# Interfaces.net
KiCad netlist of a schematic drawn in Altium Designer
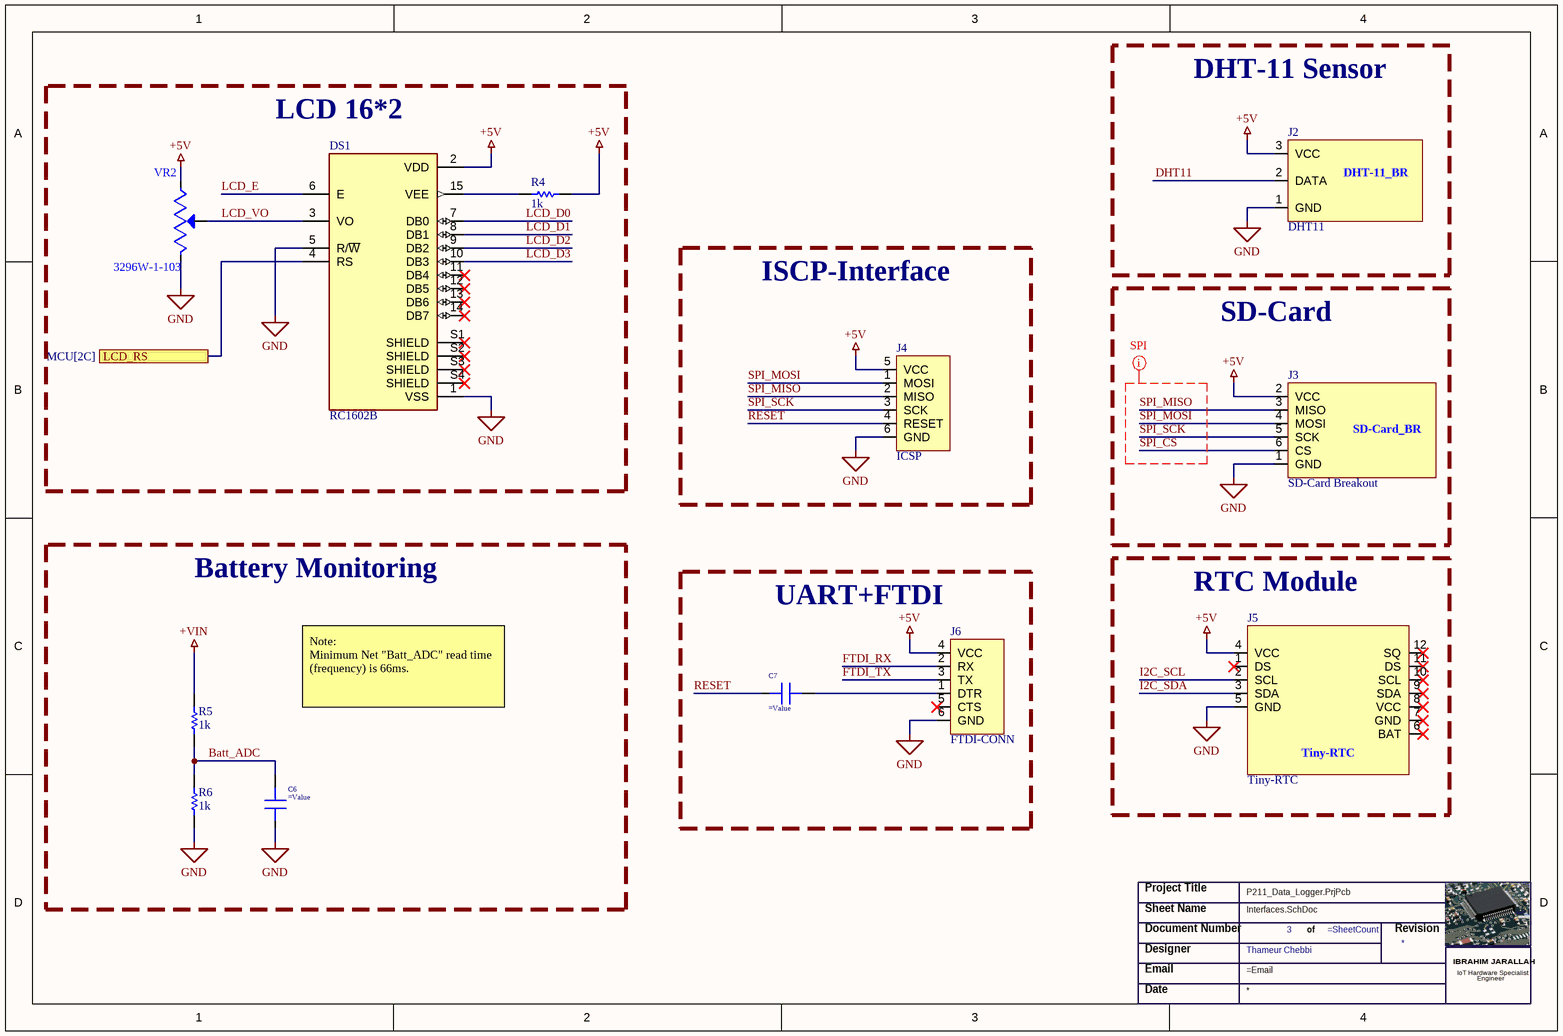
[diagram p0: Interfaces.SchDoc]

(export (version "E")
  (design (tool "Eeschema 10.0.6"))
  (components
    (comp (ref "C6")
      (value "~")
      (footprint "C 0805(2012)x0.85")
      (description "SMD 0805     50V X7R 10%")
      (fields (field (name "MANUFACTURER") "Samsung") (field (name "PUBLISHER") "Hefest"))
      (libsource (lib "SCH_THA") (part "C 0805    50V X7R - 0*"))
    )
    (comp (ref "C7")
      (value "~")
      (footprint "C 0805(2012)x0.85")
      (description "SMD 0805     50V X7R 10%")
      (fields (field (name "MANUFACTURER") "Samsung") (field (name "PUBLISHER") "Hefest"))
      (libsource (lib "SCH_THA") (part "C 0805    50V X7R - 0*"))
    )
    (comp (ref "DS1")
      (value "RC1602B")
      (footprint "LCD_RC1602B-BIW-CSV")
      (description "Display: LCD; alphanumeric; STN Negative; 16x2; blue; LED; PIN: 16")
      (fields (field (name "MF") "{'manufacturer': u'Raystar'}") (field (name "MP") "RC1602B-BIW-CSV"))
      (libsource (lib "SCH_THA") (part "RC1602B-BIW-CSV"))
    )
    (comp (ref "J2") (value "DHT11") (footprint "DHT11-BREAKOUT") (libsource (lib "SCH_THA") (part "DHT11")))
    (comp (ref "J3")
      (value "SD-Card Breakout")
      (footprint "SD-Card Breakout")
      (libsource (lib "SCH_THA") (part "SD-Card Breakout"))
    )
    (comp (ref "J4")
      (value "ICSP")
      (footprint "FTDI")
      (description "ICSP-CONN")
      (libsource (lib "SCH_THA") (part "ICSP"))
    )
    (comp (ref "J5")
      (value "Tiny-RTC")
      (footprint "Tiny-RTC")
      (libsource (lib "SCH_THA") (part "Tiny-RTC Breakout Board"))
    )
    (comp (ref "J6") (value "FTDI-CONN") (footprint "FTDI") (libsource (lib "SCH_THA") (part "FTDI")))
    (comp (ref "R4")
      (value "1k")
      (footprint "RESC2013X50X30LL20T20")
      (libsource (lib "SCH_THA") (part "RES-0805-SMD"))
    )
    (comp (ref "R5")
      (value "1k")
      (footprint "FP-CRCW1206-e3-IPC_B")
      (libsource (lib "SCH_THA") (part "RES-1206-SMD"))
    )
    (comp (ref "R6")
      (value "1k")
      (footprint "FP-CRCW1206-e3-IPC_B")
      (libsource (lib "SCH_THA") (part "RES-1206-SMD"))
    )
    (comp (ref "VR2")
      (value "3296W-1-103")
      (footprint "TRIM_3296W-1-103")
      (fields (field (name "MF") "{'manufacturer': u'Bourns'}"))
      (libsource (lib "3296W-1-103") (part "3296W-1-103"))
    )
  )
  (nets
    (net (code "1") (name "+5V") (class "Default")
      (node (ref "DS1") (pin "2") (pinfunction "VDD_2") (pintype "power_in"))
      (node (ref "J2") (pin "3") (pinfunction "VCC_3") (pintype "passive"))
      (node (ref "J3") (pin "2") (pinfunction "VCC_2") (pintype "passive"))
      (node (ref "J4") (pin "5") (pinfunction "VCC_5") (pintype "passive"))
      (node (ref "J5") (pin "4") (pinfunction "VCC_4") (pintype "passive"))
      (node (ref "J6") (pin "4") (pinfunction "VCC_4") (pintype "power_in"))
      (node (ref "R4") (pin "1") (pinfunction "1_1") (pintype "passive"))
      (node (ref "VR2") (pin "3") (pinfunction "CW_3") (pintype "passive"))
    )
    (net (code "2") (name "+VIN") (class "Default")
      (node (ref "R5") (pin "2") (pinfunction "2_2") (pintype "passive"))
    )
    (net (code "3") (name "/Batt_ADC") (class "Default")
      (node (ref "C6") (pin "2") (pinfunction "2_2") (pintype "passive"))
      (node (ref "R5") (pin "1") (pinfunction "1_1") (pintype "passive"))
      (node (ref "R6") (pin "2") (pinfunction "2_2") (pintype "passive"))
    )
    (net (code "4") (name "/DHT11") (class "Default")
      (node (ref "J2") (pin "2") (pinfunction "DATA_2") (pintype "passive"))
    )
    (net (code "5") (name "/FTDI_RX") (class "Default")
      (node (ref "J6") (pin "2") (pinfunction "RX_2") (pintype "passive"))
    )
    (net (code "6") (name "/FTDI_TX") (class "Default")
      (node (ref "J6") (pin "3") (pinfunction "TX_3") (pintype "passive"))
    )
    (net (code "7") (name "/I2C_SCL") (class "Default")
      (node (ref "J5") (pin "2") (pinfunction "SCL_2") (pintype "passive"))
    )
    (net (code "8") (name "/I2C_SDA") (class "Default")
      (node (ref "J5") (pin "3") (pinfunction "SDA_3") (pintype "passive"))
    )
    (net (code "9") (name "/LCD_D0") (class "Default")
      (node (ref "DS1") (pin "7") (pinfunction "DB0_7") (pintype "bidirectional"))
    )
    (net (code "10") (name "/LCD_D1") (class "Default")
      (node (ref "DS1") (pin "8") (pinfunction "DB1_8") (pintype "bidirectional"))
    )
    (net (code "11") (name "/LCD_D2") (class "Default")
      (node (ref "DS1") (pin "9") (pinfunction "DB2_9") (pintype "bidirectional"))
    )
    (net (code "12") (name "/LCD_D3") (class "Default")
      (node (ref "DS1") (pin "10") (pinfunction "DB3_10") (pintype "bidirectional"))
    )
    (net (code "13") (name "/LCD_E") (class "Default")
      (node (ref "DS1") (pin "6") (pinfunction "E_6") (pintype "passive"))
    )
    (net (code "14") (name "/LCD_RS") (class "Default")
      (node (ref "DS1") (pin "4") (pinfunction "RS_4") (pintype "passive"))
    )
    (net (code "15") (name "/LCD_VO") (class "Default")
      (node (ref "DS1") (pin "3") (pinfunction "VO_3") (pintype "passive"))
      (node (ref "VR2") (pin "2") (pinfunction "WIPER_2") (pintype "passive"))
    )
    (net (code "16") (name "/RESET") (class "Default")
      (node (ref "C7") (pin "1") (pinfunction "1_1") (pintype "passive"))
      (node (ref "J4") (pin "4") (pinfunction "RESET_4") (pintype "power_in"))
    )
    (net (code "17") (name "/SPI_CS") (class "Default")
      (node (ref "J3") (pin "6") (pinfunction "CS_6") (pintype "passive"))
    )
    (net (code "18") (name "/SPI_MISO") (class "Default")
      (node (ref "J3") (pin "3") (pinfunction "MISO_3") (pintype "passive"))
      (node (ref "J4") (pin "2") (pinfunction "MISO_2") (pintype "passive"))
    )
    (net (code "19") (name "/SPI_MOSI") (class "Default")
      (node (ref "J3") (pin "4") (pinfunction "MOSI_4") (pintype "passive"))
      (node (ref "J4") (pin "1") (pinfunction "MOSI_1") (pintype "passive"))
    )
    (net (code "20") (name "/SPI_SCK") (class "Default")
      (node (ref "J3") (pin "5") (pinfunction "SCK_5") (pintype "passive"))
      (node (ref "J4") (pin "3") (pinfunction "SCK_3") (pintype "passive"))
    )
    (net (code "21") (name "GND") (class "Default")
      (node (ref "C6") (pin "1") (pinfunction "1_1") (pintype "passive"))
      (node (ref "DS1") (pin "1") (pinfunction "VSS_1") (pintype "power_in"))
      (node (ref "DS1") (pin "5") (pinfunction "R/~{W}_5") (pintype "passive"))
      (node (ref "J2") (pin "1") (pinfunction "GND_1") (pintype "passive"))
      (node (ref "J3") (pin "1") (pinfunction "GND_1") (pintype "passive"))
      (node (ref "J4") (pin "6") (pinfunction "GND_6") (pintype "power_in"))
      (node (ref "J5") (pin "5") (pinfunction "GND_5") (pintype "passive"))
      (node (ref "J6") (pin "6") (pinfunction "GND_6") (pintype "power_in"))
      (node (ref "R6") (pin "1") (pinfunction "1_1") (pintype "passive"))
      (node (ref "VR2") (pin "1") (pinfunction "CCW_1") (pintype "passive"))
    )
    (net (code "22") (name "Net-(DS1-VEE)") (class "Default")
      (node (ref "DS1") (pin "15") (pinfunction "VEE_15") (pintype "output"))
      (node (ref "R4") (pin "2") (pinfunction "2_2") (pintype "passive"))
    )
    (net (code "23") (name "Net-(J6-DTR)") (class "Default")
      (node (ref "C7") (pin "2") (pinfunction "2_2") (pintype "passive"))
      (node (ref "J6") (pin "1") (pinfunction "DTR_1") (pintype "passive"))
    )
    (net (code "24") (name "unconnected-(DS1-DB4-Pad11)") (class "Default")
      (node (ref "DS1") (pin "11") (pinfunction "DB4_11") (pintype "bidirectional+no_connect"))
    )
    (net (code "25") (name "unconnected-(DS1-DB5-Pad12)") (class "Default")
      (node (ref "DS1") (pin "12") (pinfunction "DB5_12") (pintype "bidirectional+no_connect"))
    )
    (net (code "26") (name "unconnected-(DS1-DB6-Pad13)") (class "Default")
      (node (ref "DS1") (pin "13") (pinfunction "DB6_13") (pintype "bidirectional+no_connect"))
    )
    (net (code "27") (name "unconnected-(DS1-DB7-Pad14)") (class "Default")
      (node (ref "DS1") (pin "14") (pinfunction "DB7_14") (pintype "bidirectional+no_connect"))
    )
    (net (code "28") (name "unconnected-(DS1-SHIELD-PadS1)") (class "Default")
      (node (ref "DS1") (pin "S1") (pinfunction "SHIELD_S1") (pintype "passive+no_connect"))
    )
    (net (code "29") (name "unconnected-(DS1-SHIELD-PadS2)") (class "Default")
      (node (ref "DS1") (pin "S2") (pinfunction "SHIELD_S2") (pintype "passive+no_connect"))
    )
    (net (code "30") (name "unconnected-(DS1-SHIELD-PadS3)") (class "Default")
      (node (ref "DS1") (pin "S3") (pinfunction "SHIELD_S3") (pintype "passive+no_connect"))
    )
    (net (code "31") (name "unconnected-(DS1-SHIELD-PadS4)") (class "Default")
      (node (ref "DS1") (pin "S4") (pinfunction "SHIELD_S4") (pintype "passive+no_connect"))
    )
    (net (code "32") (name "unconnected-(J5-BAT-Pad6)") (class "Default")
      (node (ref "J5") (pin "6") (pinfunction "BAT_6") (pintype "passive+no_connect"))
    )
    (net (code "33") (name "unconnected-(J5-DS-Pad1)") (class "Default")
      (node (ref "J5") (pin "1") (pinfunction "DS_1") (pintype "passive+no_connect"))
    )
    (net (code "34") (name "unconnected-(J5-DS-Pad11)") (class "Default")
      (node (ref "J5") (pin "11") (pinfunction "DS_11") (pintype "passive+no_connect"))
    )
    (net (code "35") (name "unconnected-(J5-GND-Pad7)") (class "Default")
      (node (ref "J5") (pin "7") (pinfunction "GND_7") (pintype "passive+no_connect"))
    )
    (net (code "36") (name "unconnected-(J5-SCL-Pad10)") (class "Default")
      (node (ref "J5") (pin "10") (pinfunction "SCL_10") (pintype "passive+no_connect"))
    )
    (net (code "37") (name "unconnected-(J5-SDA-Pad9)") (class "Default")
      (node (ref "J5") (pin "9") (pinfunction "SDA_9") (pintype "passive+no_connect"))
    )
    (net (code "38") (name "unconnected-(J5-SQ-Pad12)") (class "Default")
      (node (ref "J5") (pin "12") (pinfunction "SQ_12") (pintype "passive+no_connect"))
    )
    (net (code "39") (name "unconnected-(J5-VCC-Pad8)") (class "Default")
      (node (ref "J5") (pin "8") (pinfunction "VCC_8") (pintype "passive+no_connect"))
    )
    (net (code "40") (name "unconnected-(J6-CTS-Pad5)") (class "Default")
      (node (ref "J6") (pin "5") (pinfunction "CTS_5") (pintype "passive+no_connect"))
    )
  )
)
